# ECU.net
KiCad netlist of a schematic drawn in Altium Designer
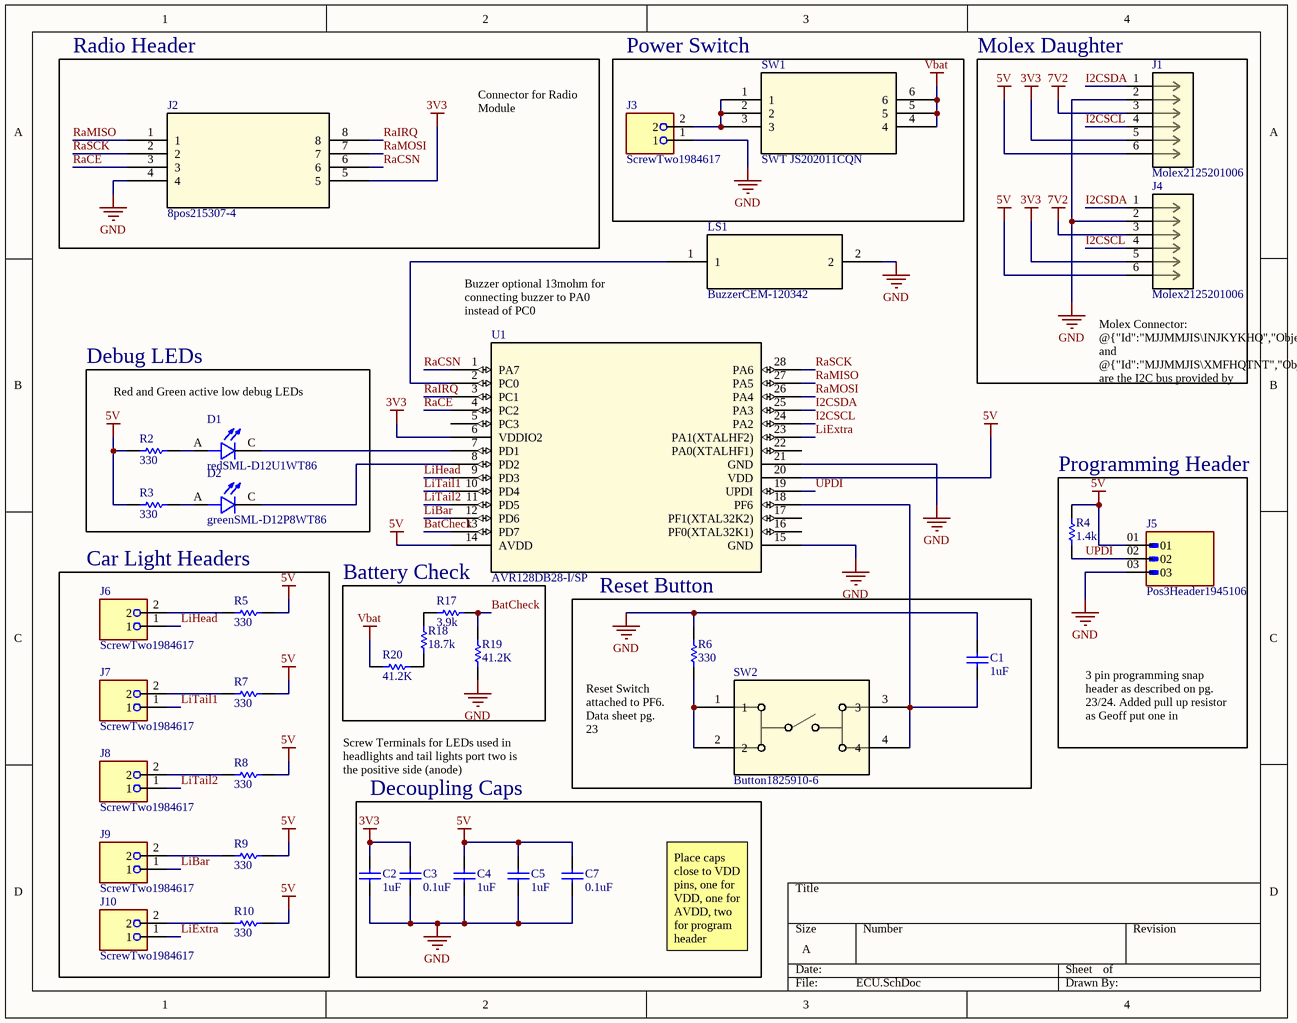
[diagram p0: ECU.SchDoc]

(export (version "E")
  (design (tool "Eeschema 10.0.6"))
  (components
    (comp (ref "C1")
      (value "1uF")
      (footprint "RES 0805")
      (fields
        (field (name "MANUFACTURER") "Samsung")
        (field (name "MANUFACTURER PART NUMBER") "CL21B105KBFNNNE")
      )
      (libsource (lib "Schlib1") (part "CAP CER 1uF 10% 50V 0805"))
    )
    (comp (ref "C2")
      (value "1uF")
      (footprint "RES 0805")
      (fields
        (field (name "MANUFACTURER") "Samsung")
        (field (name "MANUFACTURER PART NUMBER") "CL21B105KBFNNNE")
      )
      (libsource (lib "Schlib1") (part "CAP CER 1uF 10% 50V 0805"))
    )
    (comp (ref "C3")
      (value "0.1uF")
      (footprint "RES 0805")
      (fields
        (field (name "MANUFACTURER") "Yageo")
        (field (name "MANUFACTURER PART NUMBER") "CC0805KRX7R9BB104")
      )
      (libsource (lib "Schlib1") (part "CAP CER 0.1uF 10% 50V 0805"))
    )
    (comp (ref "C4")
      (value "1uF")
      (footprint "RES 0805")
      (fields
        (field (name "MANUFACTURER") "Samsung")
        (field (name "MANUFACTURER PART NUMBER") "CL21B105KBFNNNE")
      )
      (libsource (lib "Schlib1") (part "CAP CER 1uF 10% 50V 0805"))
    )
    (comp (ref "C5")
      (value "1uF")
      (footprint "RES 0805")
      (fields
        (field (name "MANUFACTURER") "Samsung")
        (field (name "MANUFACTURER PART NUMBER") "CL21B105KBFNNNE")
      )
      (libsource (lib "Schlib1") (part "CAP CER 1uF 10% 50V 0805"))
    )
    (comp (ref "C7")
      (value "0.1uF")
      (footprint "RES 0805")
      (fields
        (field (name "MANUFACTURER") "Yageo")
        (field (name "MANUFACTURER PART NUMBER") "CC0805KRX7R9BB104")
      )
      (libsource (lib "Schlib1") (part "CAP CER 0.1uF 10% 50V 0805"))
    )
    (comp (ref "D1")
      (value "redSML-D12U1WT86")
      (footprint "0603LED")
      (description "Single Color LED, Red, Milky White, 1.2mm")
      (fields (field (name "MANUFACTURER") "Rohm") (field (name "MANUFACTURER PART NUMBER") "SML-D12U1WT86"))
      (libsource (lib "Schlib1") (part "redSML-D12U1WT86"))
    )
    (comp (ref "D2")
      (value "greenSML-D12P8WT86")
      (footprint "0603LED")
      (description "Single Color LED, Pure Green, Diffused Milky White, 1.2mm")
      (fields (field (name "MANUFACTURER") "Rohm") (field (name "MANUFACTURER PART NUMBER") "SML-D12P8WT86"))
      (libsource (lib "Schlib1") (part "greenSML-D12P8WT86"))
    )
    (comp (ref "J1")
      (value "Molex2125201006")
      (footprint "Molex2125201006")
      (description "Connector Power Header 6 Position 4.2mm Solder Through Hole Tray")
      (fields (field (name "MANUFACTURER") "Molex") (field (name "MANUFACTURER PART NUMBER") "212520-1006"))
      (libsource (lib "Schlib1") (part "Molex2125201006"))
    )
    (comp (ref "J2")
      (value "8pos215307-4")
      (footprint "215307-4")
      (fields
        (field (name "MANUFACTURER") "TE Connectivity")
        (field (name "MANUFACTURER PART NUMBER") "215307-4")
      )
      (libsource (lib "Schlib1") (part "8pos215307-4"))
    )
    (comp (ref "J3")
      (value "ScrewTwo1984617")
      (footprint "PHOENIX_1984617")
      (description "Barrier Strip Terminal Block, 17.5A, 1.5mm2, 1 Row(s), 1 Deck(s)")
      (fields
        (field (name "MANUFACTURER") "Phoenix Contact")
        (field (name "MANUFACTURER PART NUMBER") "1984617")
        (field (name "SAFETY APPROVAL") "UL,CUL,EAC")
      )
      (libsource (lib "Schlib1") (part "ScrewTwo1984617"))
    )
    (comp (ref "J4")
      (value "Molex2125201006")
      (footprint "Molex2125201006")
      (description "Connector Power Header 6 Position 4.2mm Solder Through Hole Tray")
      (fields (field (name "MANUFACTURER") "Molex") (field (name "MANUFACTURER PART NUMBER") "212520-1006"))
      (libsource (lib "Schlib1") (part "Molex2125201006"))
    )
    (comp (ref "J5")
      (value "Pos3Header1945106")
      (footprint "Pos3Header")
      (description "Board Connector, 3 Contact(s), 1 Row(s), Male, Straight, Solder Terminal, Black Insulator")
      (fields
        (field (name "MANUFACTURER") "Phoenix Contact")
        (field (name "MANUFACTURER PART NUMBER") "PST1,0/3-3,5")
      )
      (libsource (lib "Schlib1") (part "Pos3Header1945106"))
    )
    (comp (ref "J6")
      (value "ScrewTwo1984617")
      (footprint "PHOENIX_1984617")
      (description "Barrier Strip Terminal Block, 17.5A, 1.5mm2, 1 Row(s), 1 Deck(s)")
      (fields
        (field (name "MANUFACTURER") "Phoenix Contact")
        (field (name "MANUFACTURER PART NUMBER") "1984617")
        (field (name "SAFETY APPROVAL") "UL,CUL,EAC")
      )
      (libsource (lib "Schlib1") (part "ScrewTwo1984617"))
    )
    (comp (ref "J7")
      (value "ScrewTwo1984617")
      (footprint "PHOENIX_1984617")
      (description "Barrier Strip Terminal Block, 17.5A, 1.5mm2, 1 Row(s), 1 Deck(s)")
      (fields
        (field (name "MANUFACTURER") "Phoenix Contact")
        (field (name "MANUFACTURER PART NUMBER") "1984617")
        (field (name "SAFETY APPROVAL") "UL,CUL,EAC")
      )
      (libsource (lib "Schlib1") (part "ScrewTwo1984617"))
    )
    (comp (ref "J8")
      (value "ScrewTwo1984617")
      (footprint "PHOENIX_1984617")
      (description "Barrier Strip Terminal Block, 17.5A, 1.5mm2, 1 Row(s), 1 Deck(s)")
      (fields
        (field (name "MANUFACTURER") "Phoenix Contact")
        (field (name "MANUFACTURER PART NUMBER") "1984617")
        (field (name "SAFETY APPROVAL") "UL,CUL,EAC")
      )
      (libsource (lib "Schlib1") (part "ScrewTwo1984617"))
    )
    (comp (ref "J9")
      (value "ScrewTwo1984617")
      (footprint "PHOENIX_1984617")
      (description "Barrier Strip Terminal Block, 17.5A, 1.5mm2, 1 Row(s), 1 Deck(s)")
      (fields
        (field (name "MANUFACTURER") "Phoenix Contact")
        (field (name "MANUFACTURER PART NUMBER") "1984617")
        (field (name "SAFETY APPROVAL") "UL,CUL,EAC")
      )
      (libsource (lib "Schlib1") (part "ScrewTwo1984617"))
    )
    (comp (ref "J10")
      (value "ScrewTwo1984617")
      (footprint "PHOENIX_1984617")
      (description "Barrier Strip Terminal Block, 17.5A, 1.5mm2, 1 Row(s), 1 Deck(s)")
      (fields
        (field (name "MANUFACTURER") "Phoenix Contact")
        (field (name "MANUFACTURER PART NUMBER") "1984617")
        (field (name "SAFETY APPROVAL") "UL,CUL,EAC")
      )
      (libsource (lib "Schlib1") (part "ScrewTwo1984617"))
    )
    (comp (ref "LS1")
      (value "BuzzerCEM-120342")
      (footprint "CEM-1203(42)")
      (description "Audio Signaling/Alarm Devices")
      (fields
        (field (name "MANUFACTURER") "CUI Devices")
        (field (name "MANUFACTURER PART NUMBER") "CEM-1203(42)")
      )
      (libsource (lib "Schlib1") (part "BuzzerCEM-120342"))
    )
    (comp (ref "R2")
      (value "330")
      (footprint "RES 0805")
      (fields
        (field (name "MANUFACTURER") "Stackpole Electronics")
        (field (name "MANUFACTURER PART NUMBER") "RMCF0805FT330R")
        (field (name "TOLERANCE") "1%")
      )
      (libsource (lib "Schlib1") (part "RES 330 1% 0.125W 0805"))
    )
    (comp (ref "R3")
      (value "330")
      (footprint "RES 0805")
      (fields
        (field (name "MANUFACTURER") "Stackpole Electronics")
        (field (name "MANUFACTURER PART NUMBER") "RMCF0805FT330R")
        (field (name "TOLERANCE") "1%")
      )
      (libsource (lib "Schlib1") (part "RES 330 1% 0.125W 0805"))
    )
    (comp (ref "R4")
      (value "1.4k")
      (footprint "RES 0805")
      (fields
        (field (name "MANUFACTURER") "Yageo")
        (field (name "MANUFACTURER PART NUMBER") "RC0805FR-071K4L")
        (field (name "TOLERANCE") "1%")
      )
      (libsource (lib "Schlib1") (part "RES 1.4k 1% 0.125W 0805"))
    )
    (comp (ref "R5")
      (value "330")
      (footprint "RES 0805")
      (fields
        (field (name "MANUFACTURER") "Stackpole Electronics")
        (field (name "MANUFACTURER PART NUMBER") "RMCF0805FT330R")
        (field (name "TOLERANCE") "1%")
      )
      (libsource (lib "Schlib1") (part "RES 330 1% 0.125W 0805"))
    )
    (comp (ref "R6")
      (value "330")
      (footprint "RES 0805")
      (fields
        (field (name "MANUFACTURER") "Stackpole Electronics")
        (field (name "MANUFACTURER PART NUMBER") "RMCF0805FT330R")
        (field (name "TOLERANCE") "1%")
      )
      (libsource (lib "Schlib1") (part "RES 330 1% 0.125W 0805"))
    )
    (comp (ref "R7")
      (value "330")
      (footprint "RES 0805")
      (fields
        (field (name "MANUFACTURER") "Stackpole Electronics")
        (field (name "MANUFACTURER PART NUMBER") "RMCF0805FT330R")
        (field (name "TOLERANCE") "1%")
      )
      (libsource (lib "Schlib1") (part "RES 330 1% 0.125W 0805"))
    )
    (comp (ref "R8")
      (value "330")
      (footprint "RES 0805")
      (fields
        (field (name "MANUFACTURER") "Stackpole Electronics")
        (field (name "MANUFACTURER PART NUMBER") "RMCF0805FT330R")
        (field (name "TOLERANCE") "1%")
      )
      (libsource (lib "Schlib1") (part "RES 330 1% 0.125W 0805"))
    )
    (comp (ref "R9")
      (value "330")
      (footprint "RES 0805")
      (fields
        (field (name "MANUFACTURER") "Stackpole Electronics")
        (field (name "MANUFACTURER PART NUMBER") "RMCF0805FT330R")
        (field (name "TOLERANCE") "1%")
      )
      (libsource (lib "Schlib1") (part "RES 330 1% 0.125W 0805"))
    )
    (comp (ref "R10")
      (value "330")
      (footprint "RES 0805")
      (fields
        (field (name "MANUFACTURER") "Stackpole Electronics")
        (field (name "MANUFACTURER PART NUMBER") "RMCF0805FT330R")
        (field (name "TOLERANCE") "1%")
      )
      (libsource (lib "Schlib1") (part "RES 330 1% 0.125W 0805"))
    )
    (comp (ref "R17")
      (value "3.9k")
      (footprint "RES 0805")
      (fields
        (field (name "MANUFACTURER") "Stackpole Electronics")
        (field (name "MANUFACTURER PART NUMBER") "RMCF0805FT3K92")
        (field (name "TOLERANCE") "1%")
      )
      (libsource (lib "Schlib1") (part "RES 3.9k 1% 0.125W 0805"))
    )
    (comp (ref "R18")
      (value "18.7k")
      (footprint "RES 0805")
      (fields
        (field (name "MANUFACTURER") "Stackpole Electronics")
        (field (name "MANUFACTURER PART NUMBER") "RMCF0805FT18K7")
        (field (name "TOLERANCE") "1%")
      )
      (libsource (lib "Schlib1") (part "RES 18.7k 1% 0.125W 0805"))
    )
    (comp (ref "R19")
      (value "41.2K")
      (footprint "RES 0805")
      (fields
        (field (name "MANUFACTURER") "Vishay")
        (field (name "MANUFACTURER PART NUMBER") "CRCW080541K2FKEA")
        (field (name "TOLERANCE") "1%")
      )
      (libsource (lib "Schlib1") (part "RES 41.2K 1% 0.125W 0805"))
    )
    (comp (ref "R20")
      (value "41.2K")
      (footprint "RES 0805")
      (fields
        (field (name "MANUFACTURER") "Vishay")
        (field (name "MANUFACTURER PART NUMBER") "CRCW080541K2FKEA")
        (field (name "TOLERANCE") "1%")
      )
      (libsource (lib "Schlib1") (part "RES 41.2K 1% 0.125W 0805"))
    )
    (comp (ref "SW1")
      (value "SWT JS202011CQN")
      (footprint "SWTJS202011CQN")
      (fields (field (name "MANUFACTURER") "ITT C&K") (field (name "MANUFACTURER PART NUMBER") "JS202011CQN"))
      (libsource (lib "Schlib1") (part "SWT JS202011CQN"))
    )
    (comp (ref "SW2")
      (value "Button1825910-6")
      (footprint "Button1825910-6")
      (fields
        (field (name "MANUFACTURER") "TE Connectivity Alcoswitch")
        (field (name "MANUFACTURER PART NUMBER") "1825910-6")
      )
      (libsource (lib "Schlib1") (part "Button1825910-6"))
    )
    (comp (ref "U1")
      (value "AVR128DB28-I/SP")
      (footprint "AVR128DB28-ISP")
      (description "RISC Microcontroller, 8-Bit, FLASH, AVR CPU, 24MHz, CMOS, PDIP28")
      (fields (field (name "MANUFACTURER") "Microchip"))
      (libsource (lib "Schlib1") (part "AVR128DB28-I/SP"))
    )
  )
  (nets
    (net (code "1") (name "/BatCheck") (class "Default")
      (node (ref "R17") (pin "2") (pinfunction "2_2") (pintype "passive"))
      (node (ref "R19") (pin "2") (pinfunction "2_2") (pintype "passive"))
      (node (ref "U1") (pin "13") (pinfunction "PD7_13") (pintype "bidirectional"))
    )
    (net (code "2") (name "/I2CSCL") (class "Default")
      (node (ref "J1") (pin "4") (pinfunction "4_4") (pintype "passive"))
      (node (ref "J4") (pin "4") (pinfunction "4_4") (pintype "passive"))
      (node (ref "U1") (pin "24") (pinfunction "PA2_24") (pintype "bidirectional"))
    )
    (net (code "3") (name "/I2CSDA") (class "Default")
      (node (ref "J1") (pin "1") (pinfunction "1_1") (pintype "passive"))
      (node (ref "J4") (pin "1") (pinfunction "1_1") (pintype "passive"))
      (node (ref "U1") (pin "25") (pinfunction "PA3_25") (pintype "bidirectional"))
    )
    (net (code "4") (name "/LiBar") (class "Default")
      (node (ref "J9") (pin "1") (pinfunction "1_1") (pintype "passive"))
      (node (ref "U1") (pin "12") (pinfunction "PD6_12") (pintype "bidirectional"))
    )
    (net (code "5") (name "/LiExtra") (class "Default")
      (node (ref "J10") (pin "1") (pinfunction "1_1") (pintype "passive"))
      (node (ref "U1") (pin "23") (pinfunction "PA1(XTALHF2)_23") (pintype "bidirectional"))
    )
    (net (code "6") (name "/LiHead") (class "Default")
      (node (ref "J6") (pin "1") (pinfunction "1_1") (pintype "passive"))
      (node (ref "U1") (pin "9") (pinfunction "PD3_9") (pintype "bidirectional"))
    )
    (net (code "7") (name "/LiTail1") (class "Default")
      (node (ref "J7") (pin "1") (pinfunction "1_1") (pintype "passive"))
      (node (ref "U1") (pin "10") (pinfunction "PD4_10") (pintype "bidirectional"))
    )
    (net (code "8") (name "/LiTail2") (class "Default")
      (node (ref "J8") (pin "1") (pinfunction "1_1") (pintype "passive"))
      (node (ref "U1") (pin "11") (pinfunction "PD5_11") (pintype "bidirectional"))
    )
    (net (code "9") (name "/RaCE") (class "Default")
      (node (ref "J2") (pin "3") (pinfunction "3_3") (pintype "passive"))
      (node (ref "U1") (pin "4") (pinfunction "PC2_4") (pintype "bidirectional"))
    )
    (net (code "10") (name "/RaCSN") (class "Default")
      (node (ref "J2") (pin "6") (pinfunction "6_6") (pintype "passive"))
      (node (ref "U1") (pin "1") (pinfunction "PA7_1") (pintype "bidirectional"))
    )
    (net (code "11") (name "/RaIRQ") (class "Default")
      (node (ref "J2") (pin "8") (pinfunction "8_8") (pintype "passive"))
      (node (ref "U1") (pin "3") (pinfunction "PC1_3") (pintype "bidirectional"))
    )
    (net (code "12") (name "/RaMISO") (class "Default")
      (node (ref "J2") (pin "1") (pinfunction "1_1") (pintype "passive"))
      (node (ref "U1") (pin "27") (pinfunction "PA5_27") (pintype "bidirectional"))
    )
    (net (code "13") (name "/RaMOSI") (class "Default")
      (node (ref "J2") (pin "7") (pinfunction "7_7") (pintype "passive"))
      (node (ref "U1") (pin "26") (pinfunction "PA4_26") (pintype "bidirectional"))
    )
    (net (code "14") (name "/RaSCK") (class "Default")
      (node (ref "J2") (pin "2") (pinfunction "2_2") (pintype "passive"))
      (node (ref "U1") (pin "28") (pinfunction "PA6_28") (pintype "bidirectional"))
    )
    (net (code "15") (name "/UPDI") (class "Default")
      (node (ref "J5") (pin "02") (pinfunction "02_02") (pintype "passive"))
      (node (ref "R4") (pin "1") (pinfunction "1_1") (pintype "passive"))
      (node (ref "U1") (pin "19") (pinfunction "UPDI_19") (pintype "bidirectional"))
    )
    (net (code "16") (name "3V3") (class "Default")
      (node (ref "C2") (pin "2") (pinfunction "2_2") (pintype "passive"))
      (node (ref "C3") (pin "2") (pinfunction "2_2") (pintype "passive"))
      (node (ref "J1") (pin "5") (pinfunction "5_5") (pintype "passive"))
      (node (ref "J2") (pin "5") (pinfunction "5_5") (pintype "passive"))
      (node (ref "J4") (pin "5") (pinfunction "5_5") (pintype "passive"))
      (node (ref "U1") (pin "6") (pinfunction "VDDIO2_6") (pintype "power_in"))
    )
    (net (code "17") (name "5V") (class "Default")
      (node (ref "C4") (pin "2") (pinfunction "2_2") (pintype "passive"))
      (node (ref "C5") (pin "1") (pinfunction "1_1") (pintype "passive"))
      (node (ref "C7") (pin "2") (pinfunction "2_2") (pintype "passive"))
      (node (ref "J1") (pin "6") (pinfunction "6_6") (pintype "passive"))
      (node (ref "J4") (pin "6") (pinfunction "6_6") (pintype "passive"))
      (node (ref "J5") (pin "01") (pinfunction "01_01") (pintype "passive"))
      (node (ref "R10") (pin "2") (pinfunction "2_2") (pintype "passive"))
      (node (ref "R2") (pin "1") (pinfunction "1_1") (pintype "passive"))
      (node (ref "R3") (pin "1") (pinfunction "1_1") (pintype "passive"))
      (node (ref "R4") (pin "2") (pinfunction "2_2") (pintype "passive"))
      (node (ref "R5") (pin "2") (pinfunction "2_2") (pintype "passive"))
      (node (ref "R7") (pin "2") (pinfunction "2_2") (pintype "passive"))
      (node (ref "R8") (pin "2") (pinfunction "2_2") (pintype "passive"))
      (node (ref "R9") (pin "2") (pinfunction "2_2") (pintype "passive"))
      (node (ref "U1") (pin "14") (pinfunction "AVDD_14") (pintype "power_in"))
      (node (ref "U1") (pin "20") (pinfunction "VDD_20") (pintype "power_in"))
    )
    (net (code "18") (name "7V2") (class "Default")
      (node (ref "J1") (pin "3") (pinfunction "3_3") (pintype "passive"))
      (node (ref "J4") (pin "3") (pinfunction "3_3") (pintype "passive"))
    )
    (net (code "19") (name "GND") (class "Default")
      (node (ref "C1") (pin "2") (pinfunction "2_2") (pintype "passive"))
      (node (ref "C2") (pin "1") (pinfunction "1_1") (pintype "passive"))
      (node (ref "C3") (pin "1") (pinfunction "1_1") (pintype "passive"))
      (node (ref "C4") (pin "1") (pinfunction "1_1") (pintype "passive"))
      (node (ref "C5") (pin "2") (pinfunction "2_2") (pintype "passive"))
      (node (ref "C7") (pin "1") (pinfunction "1_1") (pintype "passive"))
      (node (ref "J1") (pin "2") (pinfunction "2_2") (pintype "passive"))
      (node (ref "J2") (pin "4") (pinfunction "4_4") (pintype "passive"))
      (node (ref "J3") (pin "1") (pinfunction "1_1") (pintype "passive"))
      (node (ref "J4") (pin "2") (pinfunction "2_2") (pintype "passive"))
      (node (ref "J5") (pin "03") (pinfunction "03_03") (pintype "passive"))
      (node (ref "LS1") (pin "2") (pinfunction "2_2") (pintype "passive"))
      (node (ref "R19") (pin "1") (pinfunction "1_1") (pintype "passive"))
      (node (ref "R6") (pin "2") (pinfunction "2_2") (pintype "passive"))
      (node (ref "U1") (pin "15") (pinfunction "GND_15") (pintype "power_in"))
      (node (ref "U1") (pin "21") (pinfunction "GND_21") (pintype "power_in"))
    )
    (net (code "20") (name "Net-(D1-PadA)") (class "Default")
      (node (ref "D1") (pin "A") (pinfunction "A_A") (pintype "passive"))
      (node (ref "R2") (pin "2") (pinfunction "2_2") (pintype "passive"))
    )
    (net (code "21") (name "Net-(D2-PadA)") (class "Default")
      (node (ref "D2") (pin "A") (pinfunction "A_A") (pintype "passive"))
      (node (ref "R3") (pin "2") (pinfunction "2_2") (pintype "passive"))
    )
    (net (code "22") (name "Net-(J3-Pad2)") (class "Default")
      (node (ref "J3") (pin "2") (pinfunction "2_2") (pintype "passive"))
      (node (ref "SW1") (pin "1") (pinfunction "1_1") (pintype "passive"))
      (node (ref "SW1") (pin "2") (pinfunction "2_2") (pintype "passive"))
      (node (ref "SW1") (pin "3") (pinfunction "3_3") (pintype "passive"))
    )
    (net (code "23") (name "Net-(J6-Pad2)") (class "Default")
      (node (ref "J6") (pin "2") (pinfunction "2_2") (pintype "passive"))
      (node (ref "R5") (pin "1") (pinfunction "1_1") (pintype "passive"))
    )
    (net (code "24") (name "Net-(J7-Pad2)") (class "Default")
      (node (ref "J7") (pin "2") (pinfunction "2_2") (pintype "passive"))
      (node (ref "R7") (pin "1") (pinfunction "1_1") (pintype "passive"))
    )
    (net (code "25") (name "Net-(J8-Pad2)") (class "Default")
      (node (ref "J8") (pin "2") (pinfunction "2_2") (pintype "passive"))
      (node (ref "R8") (pin "1") (pinfunction "1_1") (pintype "passive"))
    )
    (net (code "26") (name "Net-(J9-Pad2)") (class "Default")
      (node (ref "J9") (pin "2") (pinfunction "2_2") (pintype "passive"))
      (node (ref "R9") (pin "1") (pinfunction "1_1") (pintype "passive"))
    )
    (net (code "27") (name "Net-(J10-Pad2)") (class "Default")
      (node (ref "J10") (pin "2") (pinfunction "2_2") (pintype "passive"))
      (node (ref "R10") (pin "1") (pinfunction "1_1") (pintype "passive"))
    )
    (net (code "28") (name "Net-(R6-Pad1)") (class "Default")
      (node (ref "R6") (pin "1") (pinfunction "1_1") (pintype "passive"))
      (node (ref "SW2") (pin "1") (pinfunction "1_1") (pintype "passive"))
      (node (ref "SW2") (pin "2") (pinfunction "2_2") (pintype "passive"))
    )
    (net (code "29") (name "Net-(R17-Pad1)") (class "Default")
      (node (ref "R17") (pin "1") (pinfunction "1_1") (pintype "passive"))
      (node (ref "R18") (pin "1") (pinfunction "1_1") (pintype "passive"))
    )
    (net (code "30") (name "Net-(R18-Pad2)") (class "Default")
      (node (ref "R18") (pin "2") (pinfunction "2_2") (pintype "passive"))
      (node (ref "R20") (pin "1") (pinfunction "1_1") (pintype "passive"))
    )
    (net (code "31") (name "Net-(U1-PC0)") (class "Default")
      (node (ref "LS1") (pin "1") (pinfunction "1_1") (pintype "passive"))
      (node (ref "U1") (pin "2") (pinfunction "PC0_2") (pintype "bidirectional"))
    )
    (net (code "32") (name "Net-(U1-PD1)") (class "Default")
      (node (ref "D1") (pin "C") (pinfunction "C_C") (pintype "passive"))
      (node (ref "U1") (pin "7") (pinfunction "PD1_7") (pintype "bidirectional"))
    )
    (net (code "33") (name "Net-(U1-PD2)") (class "Default")
      (node (ref "D2") (pin "C") (pinfunction "C_C") (pintype "passive"))
      (node (ref "U1") (pin "8") (pinfunction "PD2_8") (pintype "bidirectional"))
    )
    (net (code "34") (name "Net-(U1-PF6)") (class "Default")
      (node (ref "C1") (pin "1") (pinfunction "1_1") (pintype "passive"))
      (node (ref "SW2") (pin "3") (pinfunction "3_3") (pintype "passive"))
      (node (ref "SW2") (pin "4") (pinfunction "4_4") (pintype "passive"))
      (node (ref "U1") (pin "18") (pinfunction "PF6_18") (pintype "bidirectional"))
    )
    (net (code "35") (name "Vbat") (class "Default")
      (node (ref "R20") (pin "2") (pinfunction "2_2") (pintype "passive"))
      (node (ref "SW1") (pin "4") (pinfunction "4_4") (pintype "passive"))
      (node (ref "SW1") (pin "5") (pinfunction "5_5") (pintype "passive"))
      (node (ref "SW1") (pin "6") (pinfunction "6_6") (pintype "passive"))
    )
    (net (code "36") (name "unconnected-(U1-PA0(XTALHF1)-Pad22)") (class "Default")
      (node (ref "U1") (pin "22") (pinfunction "PA0(XTALHF1)_22") (pintype "bidirectional"))
    )
    (net (code "37") (name "unconnected-(U1-PC3-Pad5)") (class "Default")
      (node (ref "U1") (pin "5") (pinfunction "PC3_5") (pintype "bidirectional"))
    )
    (net (code "38") (name "unconnected-(U1-PF0(XTAL32K1)-Pad16)") (class "Default")
      (node (ref "U1") (pin "16") (pinfunction "PF0(XTAL32K1)_16") (pintype "bidirectional"))
    )
    (net (code "39") (name "unconnected-(U1-PF1(XTAL32K2)-Pad17)") (class "Default")
      (node (ref "U1") (pin "17") (pinfunction "PF1(XTAL32K2)_17") (pintype "bidirectional"))
    )
  )
)
